# TPS61022.net
KiCad netlist of a schematic drawn in Altium Designer
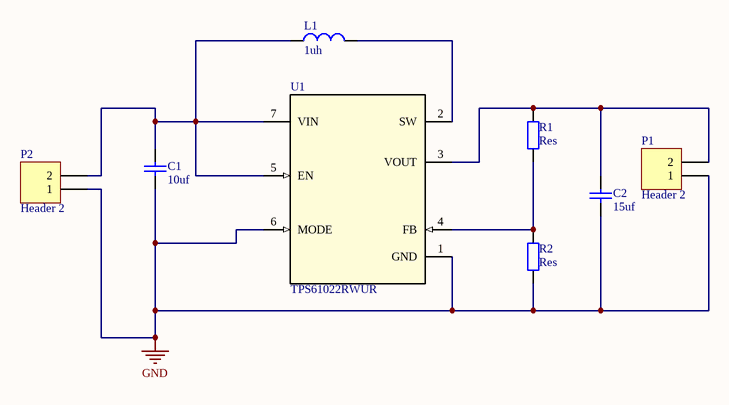
[diagram p0: TPS61022.SchDoc]

(export (version "E")
  (design (tool "Eeschema 10.0.6"))
  (components
    (comp (ref "C1")
      (value "10uf")
      (footprint "0805")
      (description "电容")
      (libsource (lib "mylib") (part "C"))
    )
    (comp (ref "C2")
      (value "15uf")
      (footprint "0805")
      (description "电容")
      (libsource (lib "mylib") (part "C"))
    )
    (comp (ref "L1")
      (value "1uh")
      (footprint "L")
      (description "大号贴片电感")
      (libsource (lib "mylib") (part "L"))
    )
    (comp (ref "P1")
      (value "Header 2")
      (footprint "HDR1X2")
      (description "Header, 2-Pin")
      (fields (field (name "PUBLISHER") "Altium Limited"))
      (libsource (lib "Miscellaneous Connectors") (part "Header 2"))
    )
    (comp (ref "P2")
      (value "Header 2")
      (footprint "HDR1X2")
      (description "Header, 2-Pin")
      (fields (field (name "PUBLISHER") "Altium Limited"))
      (libsource (lib "Miscellaneous Connectors") (part "Header 2"))
    )
    (comp (ref "R1") (value "Res") (footprint "0805") (description "电阻") (libsource (lib "mylib") (part "R")))
    (comp (ref "R2") (value "Res") (footprint "0805") (description "电阻") (libsource (lib "mylib") (part "R")))
    (comp (ref "U1")
      (value "TPS61022RWUR")
      (footprint "RWU0007A")
      (description "Imported")
      (fields (field (name "MANUFACTURER") "Texas Instruments"))
      (libsource (lib "TPS61022") (part "TPS61022RWUR"))
    )
  )
  (nets
    (net (code "1") (name "GND") (class "Default")
      (node (ref "C1") (pin "1") (pinfunction "1_1") (pintype "passive"))
      (node (ref "C2") (pin "1") (pinfunction "1_1") (pintype "passive"))
      (node (ref "P1") (pin "1") (pinfunction "1_1") (pintype "passive"))
      (node (ref "P2") (pin "1") (pinfunction "1_1") (pintype "passive"))
      (node (ref "R2") (pin "1") (pinfunction "1_1") (pintype "passive"))
      (node (ref "U1") (pin "1") (pinfunction "GND_1") (pintype "power_in"))
      (node (ref "U1") (pin "6") (pinfunction "MODE_6") (pintype "input"))
    )
    (net (code "2") (name "Net-(U1-EN)") (class "Default")
      (node (ref "C1") (pin "2") (pinfunction "2_2") (pintype "passive"))
      (node (ref "L1") (pin "1") (pinfunction "1_1") (pintype "passive"))
      (node (ref "P2") (pin "2") (pinfunction "2_2") (pintype "passive"))
      (node (ref "U1") (pin "5") (pinfunction "EN_5") (pintype "input"))
      (node (ref "U1") (pin "7") (pinfunction "VIN_7") (pintype "power_in"))
    )
    (net (code "3") (name "Net-(U1-FB)") (class "Default")
      (node (ref "R1") (pin "1") (pinfunction "1_1") (pintype "passive"))
      (node (ref "R2") (pin "2") (pinfunction "2_2") (pintype "passive"))
      (node (ref "U1") (pin "4") (pinfunction "FB_4") (pintype "input"))
    )
    (net (code "4") (name "Net-(U1-SW)") (class "Default")
      (node (ref "L1") (pin "2") (pinfunction "2_2") (pintype "passive"))
      (node (ref "U1") (pin "2") (pinfunction "SW_2") (pintype "power_in"))
    )
    (net (code "5") (name "Net-(U1-VOUT)") (class "Default")
      (node (ref "C2") (pin "2") (pinfunction "2_2") (pintype "passive"))
      (node (ref "P1") (pin "2") (pinfunction "2_2") (pintype "passive"))
      (node (ref "R1") (pin "2") (pinfunction "2_2") (pintype "passive"))
      (node (ref "U1") (pin "3") (pinfunction "VOUT_3") (pintype "power_in"))
    )
  )
)
